# Input_0.net
KiCad netlist of a schematic drawn in Altium Designer
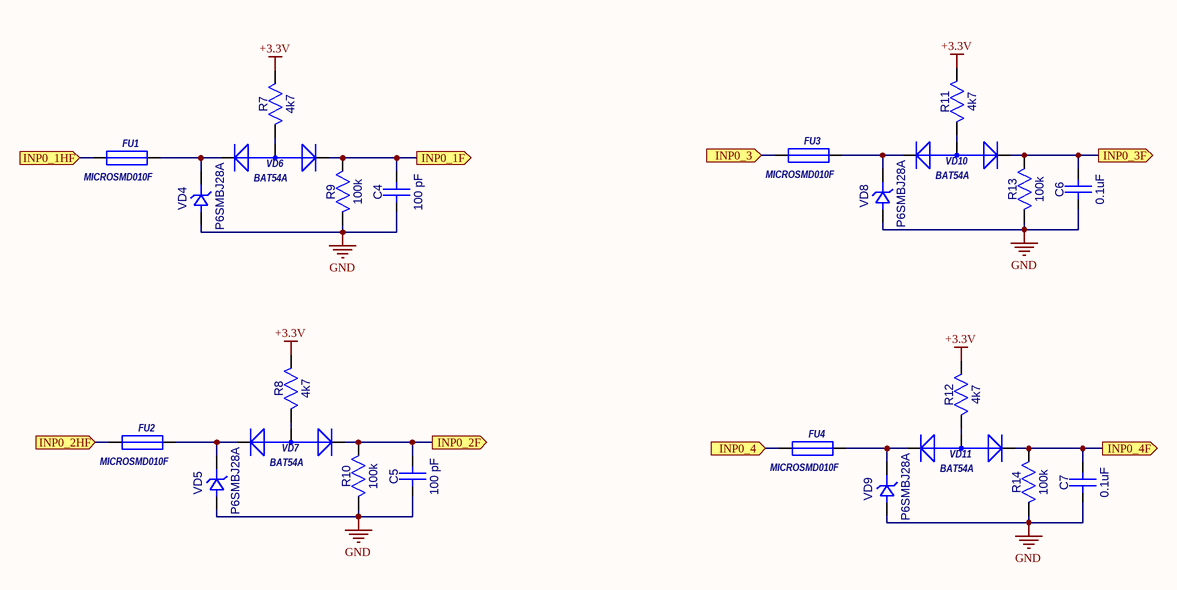
[diagram p0: Input_0.SchDoc]

(export (version "E")
  (design (tool "Eeschema 10.0.6"))
  (components
    (comp (ref "C4")
      (value "100 pF")
      (footprint "CC0603-3M")
      (description "CC0603")
      (libsource (lib "*") (part "CC0603"))
    )
    (comp (ref "C5")
      (value "100 pF")
      (footprint "CC0603-3M")
      (description "CC0603")
      (libsource (lib "*") (part "CC0603"))
    )
    (comp (ref "C6")
      (value "0.1uF")
      (footprint "CC0603-3M")
      (description "CC0603")
      (libsource (lib "*") (part "CC0603"))
    )
    (comp (ref "C7")
      (value "0.1uF")
      (footprint "CC0603-3M")
      (description "CC0603")
      (libsource (lib "*") (part "CC0603"))
    )
    (comp (ref "FU1")
      (value "MICROSMD010F")
      (footprint "RC1210")
      (description "MICROSMD")
      (libsource (lib "*") (part "MICROSMD"))
    )
    (comp (ref "FU2")
      (value "MICROSMD010F")
      (footprint "RC1210")
      (description "MICROSMD")
      (libsource (lib "*") (part "MICROSMD"))
    )
    (comp (ref "FU3")
      (value "MICROSMD010F")
      (footprint "RC1210")
      (description "MICROSMD")
      (libsource (lib "*") (part "MICROSMD"))
    )
    (comp (ref "FU4")
      (value "MICROSMD010F")
      (footprint "RC1210")
      (description "MICROSMD")
      (libsource (lib "*") (part "MICROSMD"))
    )
    (comp (ref "R7")
      (value "4k7")
      (footprint "RC0603-3M")
      (description "RC0603")
      (libsource (lib "*") (part "RC0603"))
    )
    (comp (ref "R8")
      (value "4k7")
      (footprint "RC0603-3M")
      (description "RC0603")
      (libsource (lib "*") (part "RC0603"))
    )
    (comp (ref "R9")
      (value "100k")
      (footprint "RC0603-3M")
      (description "RC0603")
      (libsource (lib "*") (part "RC0603"))
    )
    (comp (ref "R10")
      (value "100k")
      (footprint "RC0603-3M")
      (description "RC0603")
      (libsource (lib "*") (part "RC0603"))
    )
    (comp (ref "R11")
      (value "4k7")
      (footprint "RC0603-3M")
      (description "RC0603")
      (libsource (lib "*") (part "RC0603"))
    )
    (comp (ref "R12")
      (value "4k7")
      (footprint "RC0603-3M")
      (description "RC0603")
      (libsource (lib "*") (part "RC0603"))
    )
    (comp (ref "R13")
      (value "100k")
      (footprint "RC0603-3M")
      (description "RC0603")
      (libsource (lib "*") (part "RC0603"))
    )
    (comp (ref "R14")
      (value "100k")
      (footprint "RC0603-3M")
      (description "RC0603")
      (libsource (lib "*") (part "RC0603"))
    )
    (comp (ref "VD4")
      (value "P6SMBJ28A")
      (footprint "SMB")
      (description "SMBJ")
      (libsource (lib "gprs_modem") (part "SMBJ"))
    )
    (comp (ref "VD5")
      (value "P6SMBJ28A")
      (footprint "SMB")
      (description "SMBJ")
      (libsource (lib "gprs_modem") (part "SMBJ"))
    )
    (comp (ref "VD6") (value "BAT54A") (footprint "SOT-23(123)") (libsource (lib "*") (part "BAT54A")))
    (comp (ref "VD7") (value "BAT54A") (footprint "SOT-23(123)") (libsource (lib "*") (part "BAT54A")))
    (comp (ref "VD8")
      (value "P6SMBJ28A")
      (footprint "SMB")
      (description "SMBJ")
      (libsource (lib "gprs_modem") (part "SMBJ"))
    )
    (comp (ref "VD9")
      (value "P6SMBJ28A")
      (footprint "SMB")
      (description "SMBJ")
      (libsource (lib "gprs_modem") (part "SMBJ"))
    )
    (comp (ref "VD10") (value "BAT54A") (footprint "SOT-23(123)") (libsource (lib "*") (part "BAT54A")))
    (comp (ref "VD11") (value "BAT54A") (footprint "SOT-23(123)") (libsource (lib "*") (part "BAT54A")))
  )
  (nets
    (net (code "1") (name "+3.3V") (class "Default")
      (node (ref "R11") (pin "1") (pinfunction "A_1") (pintype "passive"))
      (node (ref "R12") (pin "1") (pinfunction "A_1") (pintype "passive"))
      (node (ref "R7") (pin "1") (pinfunction "A_1") (pintype "passive"))
      (node (ref "R8") (pin "1") (pinfunction "A_1") (pintype "passive"))
    )
    (net (code "2") (name "/INP0_1F") (class "Default")
      (node (ref "C4") (pin "2") (pinfunction "B_2") (pintype "passive"))
      (node (ref "R9") (pin "1") (pinfunction "A_1") (pintype "passive"))
      (node (ref "VD6") (pin "2") (pinfunction "K_2") (pintype "passive"))
    )
    (net (code "3") (name "/INP0_1HF") (class "Default") (node (ref "FU1") (pin "2") (pintype "passive")))
    (net (code "4") (name "/INP0_2F") (class "Default")
      (node (ref "C5") (pin "2") (pinfunction "B_2") (pintype "passive"))
      (node (ref "R10") (pin "1") (pinfunction "A_1") (pintype "passive"))
      (node (ref "VD7") (pin "2") (pinfunction "K_2") (pintype "passive"))
    )
    (net (code "5") (name "/INP0_2HF") (class "Default") (node (ref "FU2") (pin "2") (pintype "passive")))
    (net (code "6") (name "/INP0_3") (class "Default") (node (ref "FU3") (pin "2") (pintype "passive")))
    (net (code "7") (name "/INP0_3F") (class "Default")
      (node (ref "C6") (pin "2") (pinfunction "B_2") (pintype "passive"))
      (node (ref "R13") (pin "1") (pinfunction "A_1") (pintype "passive"))
      (node (ref "VD10") (pin "2") (pinfunction "K_2") (pintype "passive"))
    )
    (net (code "8") (name "/INP0_4") (class "Default") (node (ref "FU4") (pin "2") (pintype "passive")))
    (net (code "9") (name "/INP0_4F") (class "Default")
      (node (ref "C7") (pin "2") (pinfunction "B_2") (pintype "passive"))
      (node (ref "R14") (pin "1") (pinfunction "A_1") (pintype "passive"))
      (node (ref "VD11") (pin "2") (pinfunction "K_2") (pintype "passive"))
    )
    (net (code "10") (name "GND") (class "Default")
      (node (ref "C4") (pin "1") (pinfunction "A_1") (pintype "passive"))
      (node (ref "C5") (pin "1") (pinfunction "A_1") (pintype "passive"))
      (node (ref "C6") (pin "1") (pinfunction "A_1") (pintype "passive"))
      (node (ref "C7") (pin "1") (pinfunction "A_1") (pintype "passive"))
      (node (ref "R10") (pin "2") (pinfunction "B_2") (pintype "passive"))
      (node (ref "R13") (pin "2") (pinfunction "B_2") (pintype "passive"))
      (node (ref "R14") (pin "2") (pinfunction "B_2") (pintype "passive"))
      (node (ref "R9") (pin "2") (pinfunction "B_2") (pintype "passive"))
      (node (ref "VD4") (pin "1") (pinfunction "A_1") (pintype "passive"))
      (node (ref "VD5") (pin "1") (pinfunction "A_1") (pintype "passive"))
      (node (ref "VD8") (pin "1") (pinfunction "A_1") (pintype "passive"))
      (node (ref "VD9") (pin "1") (pinfunction "A_1") (pintype "passive"))
    )
    (net (code "11") (name "Net-(R7-B)") (class "Default")
      (node (ref "R7") (pin "2") (pinfunction "B_2") (pintype "passive"))
      (node (ref "VD6") (pin "3") (pinfunction "A_3") (pintype "passive"))
    )
    (net (code "12") (name "Net-(R8-B)") (class "Default")
      (node (ref "R8") (pin "2") (pinfunction "B_2") (pintype "passive"))
      (node (ref "VD7") (pin "3") (pinfunction "A_3") (pintype "passive"))
    )
    (net (code "13") (name "Net-(R11-B)") (class "Default")
      (node (ref "R11") (pin "2") (pinfunction "B_2") (pintype "passive"))
      (node (ref "VD10") (pin "3") (pinfunction "A_3") (pintype "passive"))
    )
    (net (code "14") (name "Net-(R12-B)") (class "Default")
      (node (ref "R12") (pin "2") (pinfunction "B_2") (pintype "passive"))
      (node (ref "VD11") (pin "3") (pinfunction "A_3") (pintype "passive"))
    )
    (net (code "15") (name "Net-(VD4-K)") (class "Default")
      (node (ref "FU1") (pin "1") (pintype "passive"))
      (node (ref "VD4") (pin "2") (pinfunction "K_2") (pintype "passive"))
      (node (ref "VD6") (pin "1") (pinfunction "K_1") (pintype "passive"))
    )
    (net (code "16") (name "Net-(VD5-K)") (class "Default")
      (node (ref "FU2") (pin "1") (pintype "passive"))
      (node (ref "VD5") (pin "2") (pinfunction "K_2") (pintype "passive"))
      (node (ref "VD7") (pin "1") (pinfunction "K_1") (pintype "passive"))
    )
    (net (code "17") (name "Net-(VD8-K)") (class "Default")
      (node (ref "FU3") (pin "1") (pintype "passive"))
      (node (ref "VD10") (pin "1") (pinfunction "K_1") (pintype "passive"))
      (node (ref "VD8") (pin "2") (pinfunction "K_2") (pintype "passive"))
    )
    (net (code "18") (name "Net-(VD9-K)") (class "Default")
      (node (ref "FU4") (pin "1") (pintype "passive"))
      (node (ref "VD11") (pin "1") (pinfunction "K_1") (pintype "passive"))
      (node (ref "VD9") (pin "2") (pinfunction "K_2") (pintype "passive"))
    )
  )
)
